# usb_tester.net
KiCad netlist of a schematic drawn in EAGLE
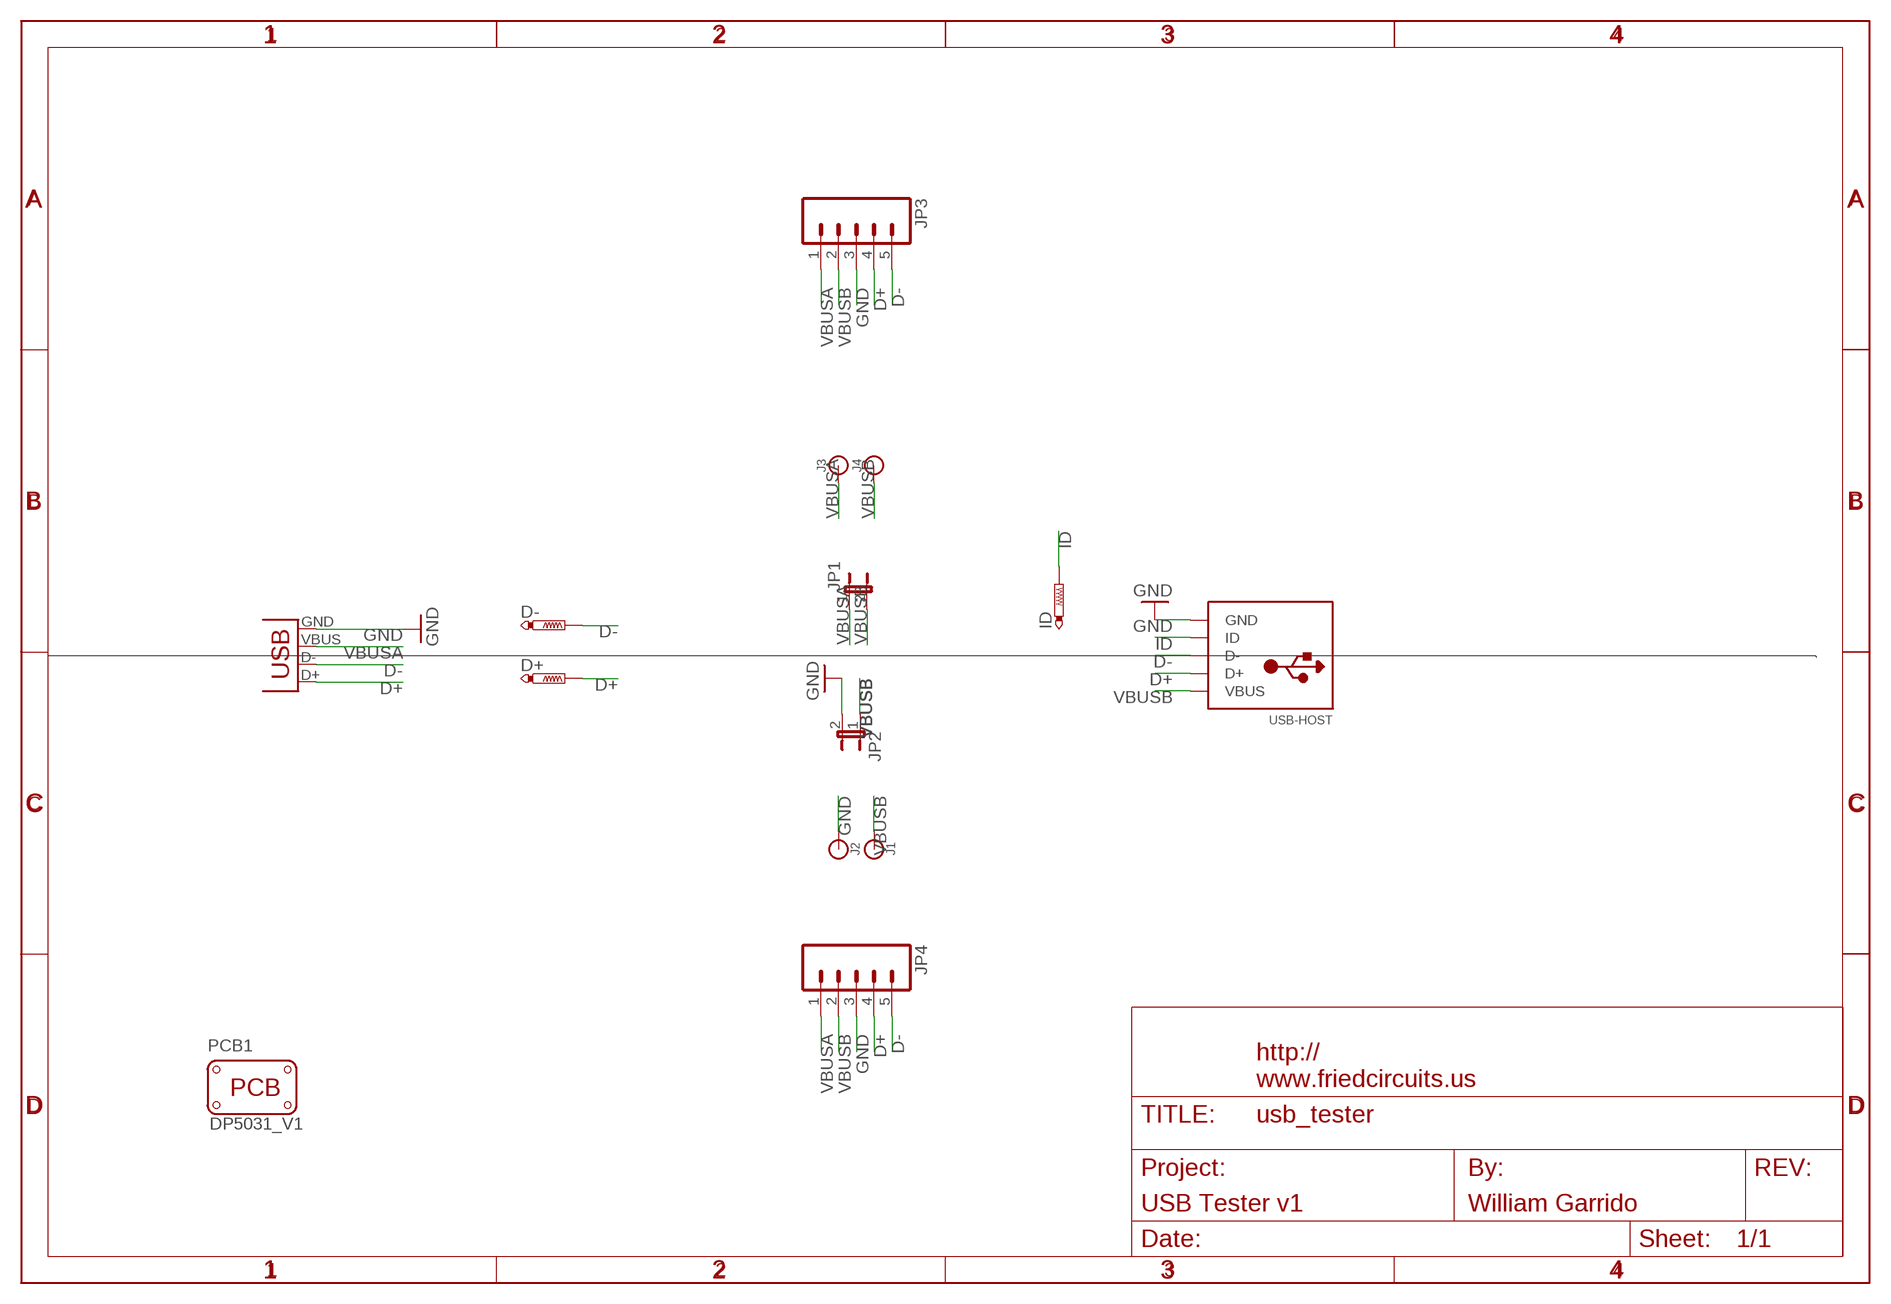
[diagram p0: schematic, sheet 1]

(export (version "E")
  (design (tool "Eeschema 10.0.6"))
  (components
    (comp (ref "D+")
      (value "PTR1PAD1-20")
      (footprint "eagle-import:P1-20")
      (libsource (lib "eagle-import") (part "PTR1PAD1-20"))
    )
    (comp (ref "D-")
      (value "PTR1PAD1-20")
      (footprint "eagle-import:P1-20")
      (libsource (lib "eagle-import") (part "PTR1PAD1-20"))
    )
    (comp (ref "ID")
      (value "PTR1PAD1-20")
      (footprint "eagle-import:P1-20")
      (libsource (lib "eagle-import") (part "PTR1PAD1-20"))
    )
    (comp (ref "J1")
      (value "BANANA_CONN")
      (footprint "eagle-import:BANANA_CONN")
      (libsource (lib "eagle-import") (part "BANANA_CONN"))
    )
    (comp (ref "J2")
      (value "BANANA_CONN")
      (footprint "eagle-import:BANANA_CONN")
      (libsource (lib "eagle-import") (part "BANANA_CONN"))
    )
    (comp (ref "J3")
      (value "BANANA_CONN")
      (footprint "eagle-import:BANANA_CONN")
      (libsource (lib "eagle-import") (part "BANANA_CONN"))
    )
    (comp (ref "J4")
      (value "BANANA_CONN")
      (footprint "eagle-import:BANANA_CONN")
      (libsource (lib "eagle-import") (part "BANANA_CONN"))
    )
    (comp (ref "JP1")
      (value "JUMPER-2PTH_LOCK")
      (footprint "eagle-import:1X02_LOCK")
      (libsource (lib "eagle-import") (part "JUMPER-2PTH_LOCK"))
    )
    (comp (ref "JP2")
      (value "JUMPER-2PTH_LOCK")
      (footprint "eagle-import:1X02_LOCK")
      (libsource (lib "eagle-import") (part "JUMPER-2PTH_LOCK"))
    )
    (comp (ref "JP3")
      (value "M05LOCK")
      (footprint "eagle-import:1X05_LOCK")
      (libsource (lib "eagle-import") (part "M05LOCK"))
    )
    (comp (ref "JP4")
      (value "M05LOCK")
      (footprint "eagle-import:1X05_LOCK")
      (libsource (lib "eagle-import") (part "M05LOCK"))
    )
    (comp (ref "PCB1")
      (value "PCB_DP_RECTANGLE-31X50")
      (footprint "eagle-import:DP5031_V1")
      (libsource (lib "eagle-import") (part "PCB_DP_RECTANGLE-31X50"))
    )
    (comp (ref "U$1")
      (value "FRAME_DINA4_L")
      (footprint "eagle-import:FC_CREDIT")
      (fields (field (name "AUTHOR") "William Garrido") (field (name "PROJECT") "USB Tester v1"))
      (libsource (lib "eagle-import") (part "FRAME_DINA4_L"))
    )
    (comp (ref "USB-DEVICE")
      (value "USB-A-SMD")
      (footprint "eagle-import:USB-A-S-NOSILK-FEMALE")
      (libsource (lib "eagle-import") (part "USB-A-SMD"))
    )
    (comp (ref "USB-HOST")
      (value "USBMINIB")
      (footprint "eagle-import:USB-MINIB")
      (libsource (lib "eagle-import") (part "USBMINIB"))
    )
  )
  (nets
    (net (code "1") (name "/D+") (class "Default")
      (node (ref "D+") (pin "TP") (pinfunction "TP_TP") (pintype "input"))
      (node (ref "JP3") (pin "4") (pinfunction "4_4") (pintype "passive"))
      (node (ref "JP4") (pin "4") (pinfunction "4_4") (pintype "passive"))
      (node (ref "USB-DEVICE") (pin "D+") (pinfunction "D+_D+") (pintype "bidirectional"))
      (node (ref "USB-HOST") (pin "D+") (pinfunction "D+_D+") (pintype "bidirectional"))
    )
    (net (code "2") (name "/D-") (class "Default")
      (node (ref "D-") (pin "TP") (pinfunction "TP_TP") (pintype "input"))
      (node (ref "JP3") (pin "5") (pinfunction "5_5") (pintype "passive"))
      (node (ref "JP4") (pin "5") (pinfunction "5_5") (pintype "passive"))
      (node (ref "USB-DEVICE") (pin "D-") (pinfunction "D-_D-") (pintype "bidirectional"))
      (node (ref "USB-HOST") (pin "D-") (pinfunction "D-_D-") (pintype "bidirectional"))
    )
    (net (code "3") (name "/ID") (class "Default")
      (node (ref "ID") (pin "TP") (pinfunction "TP_TP") (pintype "input"))
      (node (ref "USB-HOST") (pin "ID") (pinfunction "ID_ID") (pintype "bidirectional"))
    )
    (net (code "4") (name "/VBUSA") (class "Default")
      (node (ref "J3") (pin "P$1") (pinfunction "1_P$1") (pintype "passive"))
      (node (ref "JP1") (pin "1") (pinfunction "1_1") (pintype "passive"))
      (node (ref "JP3") (pin "1") (pinfunction "1_1") (pintype "passive"))
      (node (ref "JP4") (pin "1") (pinfunction "1_1") (pintype "passive"))
      (node (ref "USB-DEVICE") (pin "VBUS") (pinfunction "VBUS_VBUS") (pintype "bidirectional"))
    )
    (net (code "5") (name "/VBUSB") (class "Default")
      (node (ref "J1") (pin "P$1") (pinfunction "1_P$1") (pintype "passive"))
      (node (ref "J4") (pin "P$1") (pinfunction "1_P$1") (pintype "passive"))
      (node (ref "JP1") (pin "2") (pinfunction "2_2") (pintype "passive"))
      (node (ref "JP2") (pin "1") (pinfunction "1_1") (pintype "passive"))
      (node (ref "JP3") (pin "2") (pinfunction "2_2") (pintype "passive"))
      (node (ref "JP4") (pin "2") (pinfunction "2_2") (pintype "passive"))
      (node (ref "USB-HOST") (pin "VBUS") (pinfunction "VBUS_VBUS") (pintype "power_in"))
    )
    (net (code "6") (name "GND") (class "Default")
      (node (ref "J2") (pin "P$1") (pinfunction "1_P$1") (pintype "passive"))
      (node (ref "JP2") (pin "2") (pinfunction "2_2") (pintype "passive"))
      (node (ref "JP3") (pin "3") (pinfunction "3_3") (pintype "passive"))
      (node (ref "JP4") (pin "3") (pinfunction "3_3") (pintype "passive"))
      (node (ref "USB-DEVICE") (pin "GND") (pinfunction "GND_GND") (pintype "bidirectional"))
      (node (ref "USB-HOST") (pin "GND") (pinfunction "GND_GND") (pintype "power_in"))
    )
  )
)
